# 02_Pads_and_Knobs.net
KiCad netlist of a schematic drawn in Altium Designer
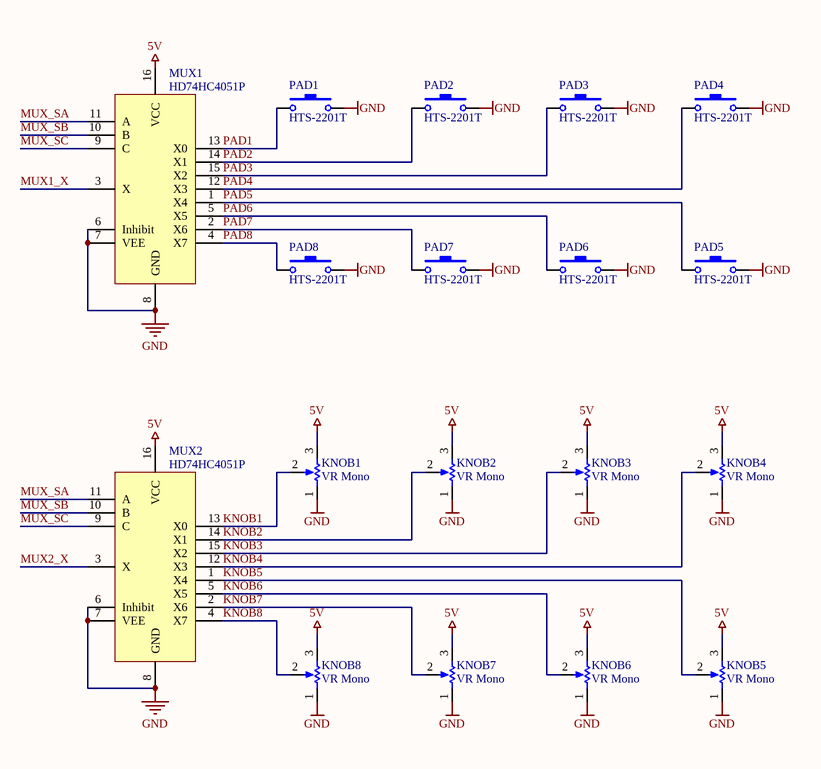
[diagram p0: 02.Pads and Knobs.SchDoc]

(export (version "E")
  (design (tool "Eeschema 10.0.6"))
  (components
    (comp (ref "KNOB1")
      (value "VR Mono")
      (footprint "RK11K113")
      (libsource (lib "Jixuan's library") (part "VR Mono"))
    )
    (comp (ref "KNOB2")
      (value "VR Mono")
      (footprint "RK11K113")
      (libsource (lib "Jixuan's library") (part "VR Mono"))
    )
    (comp (ref "KNOB3")
      (value "VR Mono")
      (footprint "RK11K113")
      (libsource (lib "Jixuan's library") (part "VR Mono"))
    )
    (comp (ref "KNOB4")
      (value "VR Mono")
      (footprint "RK11K113")
      (libsource (lib "Jixuan's library") (part "VR Mono"))
    )
    (comp (ref "KNOB5")
      (value "VR Mono")
      (footprint "RK11K113")
      (libsource (lib "Jixuan's library") (part "VR Mono"))
    )
    (comp (ref "KNOB6")
      (value "VR Mono")
      (footprint "RK11K113")
      (libsource (lib "Jixuan's library") (part "VR Mono"))
    )
    (comp (ref "KNOB7")
      (value "VR Mono")
      (footprint "RK11K113")
      (libsource (lib "Jixuan's library") (part "VR Mono"))
    )
    (comp (ref "KNOB8")
      (value "VR Mono")
      (footprint "RK11K113")
      (libsource (lib "Jixuan's library") (part "VR Mono"))
    )
    (comp (ref "MUX1")
      (value "HD74HC4051P")
      (footprint "DIP-16")
      (libsource (lib "Jixuan's library") (part "TC74HC4051AF"))
    )
    (comp (ref "MUX2")
      (value "HD74HC4051P")
      (footprint "DIP-16")
      (libsource (lib "Jixuan's library") (part "TC74HC4051AF"))
    )
    (comp (ref "PAD1")
      (value "HTS-2201T")
      (footprint "ALPS-SKHC-12mm")
      (libsource (lib "Jixuan's library") (part "Tact Switch HTS-2201T"))
    )
    (comp (ref "PAD2")
      (value "HTS-2201T")
      (footprint "ALPS-SKHC-12mm")
      (libsource (lib "Jixuan's library") (part "Tact Switch HTS-2201T"))
    )
    (comp (ref "PAD3")
      (value "HTS-2201T")
      (footprint "ALPS-SKHC-12mm")
      (libsource (lib "Jixuan's library") (part "Tact Switch HTS-2201T"))
    )
    (comp (ref "PAD4")
      (value "HTS-2201T")
      (footprint "ALPS-SKHC-12mm")
      (libsource (lib "Jixuan's library") (part "Tact Switch HTS-2201T"))
    )
    (comp (ref "PAD5")
      (value "HTS-2201T")
      (footprint "ALPS-SKHC-12mm")
      (libsource (lib "Jixuan's library") (part "Tact Switch HTS-2201T"))
    )
    (comp (ref "PAD6")
      (value "HTS-2201T")
      (footprint "ALPS-SKHC-12mm")
      (libsource (lib "Jixuan's library") (part "Tact Switch HTS-2201T"))
    )
    (comp (ref "PAD7")
      (value "HTS-2201T")
      (footprint "ALPS-SKHC-12mm")
      (libsource (lib "Jixuan's library") (part "Tact Switch HTS-2201T"))
    )
    (comp (ref "PAD8")
      (value "HTS-2201T")
      (footprint "ALPS-SKHC-12mm")
      (libsource (lib "Jixuan's library") (part "Tact Switch HTS-2201T"))
    )
  )
  (nets
    (net (code "1") (name "/KNOB1") (class "Default")
      (node (ref "KNOB1") (pin "2") (pinfunction "2_2") (pintype "passive"))
      (node (ref "MUX2") (pin "13") (pinfunction "X0_13") (pintype "passive"))
    )
    (net (code "2") (name "/KNOB2") (class "Default")
      (node (ref "KNOB2") (pin "2") (pinfunction "2_2") (pintype "passive"))
      (node (ref "MUX2") (pin "14") (pinfunction "X1_14") (pintype "passive"))
    )
    (net (code "3") (name "/KNOB3") (class "Default")
      (node (ref "KNOB3") (pin "2") (pinfunction "2_2") (pintype "passive"))
      (node (ref "MUX2") (pin "15") (pinfunction "X2_15") (pintype "passive"))
    )
    (net (code "4") (name "/KNOB4") (class "Default")
      (node (ref "KNOB4") (pin "2") (pinfunction "2_2") (pintype "passive"))
      (node (ref "MUX2") (pin "12") (pinfunction "X3_12") (pintype "passive"))
    )
    (net (code "5") (name "/KNOB5") (class "Default")
      (node (ref "KNOB5") (pin "2") (pinfunction "2_2") (pintype "passive"))
      (node (ref "MUX2") (pin "1") (pinfunction "X4_1") (pintype "passive"))
    )
    (net (code "6") (name "/KNOB6") (class "Default")
      (node (ref "KNOB6") (pin "2") (pinfunction "2_2") (pintype "passive"))
      (node (ref "MUX2") (pin "5") (pinfunction "X5_5") (pintype "passive"))
    )
    (net (code "7") (name "/KNOB7") (class "Default")
      (node (ref "KNOB7") (pin "2") (pinfunction "2_2") (pintype "passive"))
      (node (ref "MUX2") (pin "2") (pinfunction "X6_2") (pintype "passive"))
    )
    (net (code "8") (name "/KNOB8") (class "Default")
      (node (ref "KNOB8") (pin "2") (pinfunction "2_2") (pintype "passive"))
      (node (ref "MUX2") (pin "4") (pinfunction "X7_4") (pintype "passive"))
    )
    (net (code "9") (name "/MUX1_X") (class "Default")
      (node (ref "MUX1") (pin "3") (pinfunction "X_3") (pintype "passive"))
    )
    (net (code "10") (name "/MUX2_X") (class "Default")
      (node (ref "MUX2") (pin "3") (pinfunction "X_3") (pintype "passive"))
    )
    (net (code "11") (name "/MUX_SA") (class "Default")
      (node (ref "MUX1") (pin "11") (pinfunction "A_11") (pintype "passive"))
      (node (ref "MUX2") (pin "11") (pinfunction "A_11") (pintype "passive"))
    )
    (net (code "12") (name "/MUX_SB") (class "Default")
      (node (ref "MUX1") (pin "10") (pinfunction "B_10") (pintype "passive"))
      (node (ref "MUX2") (pin "10") (pinfunction "B_10") (pintype "passive"))
    )
    (net (code "13") (name "/MUX_SC") (class "Default")
      (node (ref "MUX1") (pin "9") (pinfunction "C_9") (pintype "passive"))
      (node (ref "MUX2") (pin "9") (pinfunction "C_9") (pintype "passive"))
    )
    (net (code "14") (name "/PAD1") (class "Default")
      (node (ref "MUX1") (pin "13") (pinfunction "X0_13") (pintype "passive"))
      (node (ref "PAD1") (pin "2") (pinfunction "2_2") (pintype "passive"))
    )
    (net (code "15") (name "/PAD2") (class "Default")
      (node (ref "MUX1") (pin "14") (pinfunction "X1_14") (pintype "passive"))
      (node (ref "PAD2") (pin "2") (pinfunction "2_2") (pintype "passive"))
    )
    (net (code "16") (name "/PAD3") (class "Default")
      (node (ref "MUX1") (pin "15") (pinfunction "X2_15") (pintype "passive"))
      (node (ref "PAD3") (pin "2") (pinfunction "2_2") (pintype "passive"))
    )
    (net (code "17") (name "/PAD4") (class "Default")
      (node (ref "MUX1") (pin "12") (pinfunction "X3_12") (pintype "passive"))
      (node (ref "PAD4") (pin "2") (pinfunction "2_2") (pintype "passive"))
    )
    (net (code "18") (name "/PAD5") (class "Default")
      (node (ref "MUX1") (pin "1") (pinfunction "X4_1") (pintype "passive"))
      (node (ref "PAD5") (pin "2") (pinfunction "2_2") (pintype "passive"))
    )
    (net (code "19") (name "/PAD6") (class "Default")
      (node (ref "MUX1") (pin "5") (pinfunction "X5_5") (pintype "passive"))
      (node (ref "PAD6") (pin "2") (pinfunction "2_2") (pintype "passive"))
    )
    (net (code "20") (name "/PAD7") (class "Default")
      (node (ref "MUX1") (pin "2") (pinfunction "X6_2") (pintype "passive"))
      (node (ref "PAD7") (pin "2") (pinfunction "2_2") (pintype "passive"))
    )
    (net (code "21") (name "/PAD8") (class "Default")
      (node (ref "MUX1") (pin "4") (pinfunction "X7_4") (pintype "passive"))
      (node (ref "PAD8") (pin "2") (pinfunction "2_2") (pintype "passive"))
    )
    (net (code "22") (name "5V") (class "Default")
      (node (ref "KNOB1") (pin "3") (pinfunction "3_3") (pintype "passive"))
      (node (ref "KNOB2") (pin "3") (pinfunction "3_3") (pintype "passive"))
      (node (ref "KNOB3") (pin "3") (pinfunction "3_3") (pintype "passive"))
      (node (ref "KNOB4") (pin "3") (pinfunction "3_3") (pintype "passive"))
      (node (ref "KNOB5") (pin "3") (pinfunction "3_3") (pintype "passive"))
      (node (ref "KNOB6") (pin "3") (pinfunction "3_3") (pintype "passive"))
      (node (ref "KNOB7") (pin "3") (pinfunction "3_3") (pintype "passive"))
      (node (ref "KNOB8") (pin "3") (pinfunction "3_3") (pintype "passive"))
      (node (ref "MUX1") (pin "16") (pinfunction "VCC_16") (pintype "passive"))
      (node (ref "MUX2") (pin "16") (pinfunction "VCC_16") (pintype "passive"))
    )
    (net (code "23") (name "GND") (class "Default")
      (node (ref "KNOB1") (pin "1") (pinfunction "1_1") (pintype "passive"))
      (node (ref "KNOB2") (pin "1") (pinfunction "1_1") (pintype "passive"))
      (node (ref "KNOB3") (pin "1") (pinfunction "1_1") (pintype "passive"))
      (node (ref "KNOB4") (pin "1") (pinfunction "1_1") (pintype "passive"))
      (node (ref "KNOB5") (pin "1") (pinfunction "1_1") (pintype "passive"))
      (node (ref "KNOB6") (pin "1") (pinfunction "1_1") (pintype "passive"))
      (node (ref "KNOB7") (pin "1") (pinfunction "1_1") (pintype "passive"))
      (node (ref "KNOB8") (pin "1") (pinfunction "1_1") (pintype "passive"))
      (node (ref "MUX1") (pin "6") (pinfunction "Inhibit_6") (pintype "passive"))
      (node (ref "MUX1") (pin "7") (pinfunction "VEE_7") (pintype "passive"))
      (node (ref "MUX1") (pin "8") (pinfunction "GND_8") (pintype "passive"))
      (node (ref "MUX2") (pin "6") (pinfunction "Inhibit_6") (pintype "passive"))
      (node (ref "MUX2") (pin "7") (pinfunction "VEE_7") (pintype "passive"))
      (node (ref "MUX2") (pin "8") (pinfunction "GND_8") (pintype "passive"))
      (node (ref "PAD1") (pin "1") (pinfunction "1_1") (pintype "passive"))
      (node (ref "PAD2") (pin "1") (pinfunction "1_1") (pintype "passive"))
      (node (ref "PAD3") (pin "1") (pinfunction "1_1") (pintype "passive"))
      (node (ref "PAD4") (pin "1") (pinfunction "1_1") (pintype "passive"))
      (node (ref "PAD5") (pin "1") (pinfunction "1_1") (pintype "passive"))
      (node (ref "PAD6") (pin "1") (pinfunction "1_1") (pintype "passive"))
      (node (ref "PAD7") (pin "1") (pinfunction "1_1") (pintype "passive"))
      (node (ref "PAD8") (pin "1") (pinfunction "1_1") (pintype "passive"))
    )
  )
)
